# PMU.net
KiCad netlist of a schematic drawn in Altium Designer
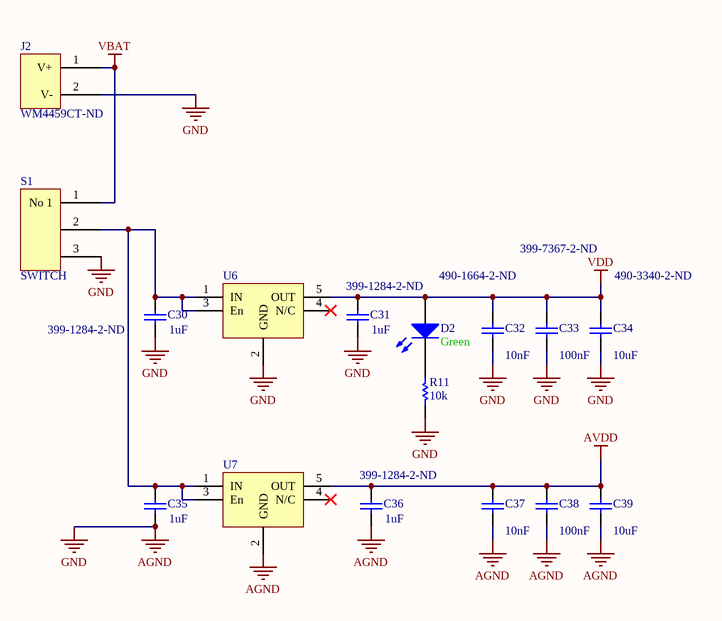
[diagram p0: PMU.SchDoc]

(export (version "E")
  (design (tool "Eeschema 10.0.6"))
  (components
    (comp (ref "C30")
      (value "1uF")
      (footprint "0402")
      (description "Capacitor (Semiconductor SIM Model)")
      (fields
        (field (name "SUPPLIER PART NUMBER 1") "399-1284-2-ND")
        (field (name "Comment") "Cap Semi")
        (field (name "PUBLISHER") "Altium Limited")
      )
      (libsource (lib "Miscellaneous Devices") (part "Cap Semi"))
    )
    (comp (ref "C31")
      (value "1uF")
      (footprint "0402")
      (description "Capacitor (Semiconductor SIM Model)")
      (fields
        (field (name "SUPPLIER PART NUMBER 1") "399-1284-2-ND")
        (field (name "Comment") "Cap Semi")
        (field (name "PUBLISHER") "Altium Limited")
      )
      (libsource (lib "Miscellaneous Devices") (part "Cap Semi"))
    )
    (comp (ref "C32")
      (value "10nF")
      (footprint "0402")
      (description "Capacitor (Semiconductor SIM Model)")
      (fields
        (field (name "SUPPLIER PART NUMBER 1") "490-1664-2-ND")
        (field (name "Comment") "Cap Semi")
        (field (name "PUBLISHER") "Altium Limited")
      )
      (libsource (lib "Miscellaneous Devices") (part "Cap Semi"))
    )
    (comp (ref "C33")
      (value "100nF")
      (footprint "0402")
      (description "Capacitor (Semiconductor SIM Model)")
      (fields
        (field (name "SUPPLIER PART NUMBER 1") "399-7367-2-ND")
        (field (name "Comment") "Cap Semi")
        (field (name "PUBLISHER") "Altium Limited")
      )
      (libsource (lib "Miscellaneous Devices") (part "Cap Semi"))
    )
    (comp (ref "C34")
      (value "10uF")
      (footprint "0402")
      (description "Capacitor (Semiconductor SIM Model)")
      (fields
        (field (name "SUPPLIER PART NUMBER 1") "490-3340-2-ND")
        (field (name "Comment") "Cap Semi")
        (field (name "PUBLISHER") "Altium Limited")
      )
      (libsource (lib "Miscellaneous Devices") (part "Cap Semi"))
    )
    (comp (ref "C35")
      (value "1uF")
      (footprint "0402")
      (description "Capacitor (Semiconductor SIM Model)")
      (fields (field (name "Comment") "Cap Semi") (field (name "PUBLISHER") "Altium Limited"))
      (libsource (lib "Miscellaneous Devices") (part "Cap Semi"))
    )
    (comp (ref "C36")
      (value "1uF")
      (footprint "0402")
      (description "Capacitor (Semiconductor SIM Model)")
      (fields
        (field (name "SUPPLIER PART NUMBER 1") "399-1284-2-ND")
        (field (name "Comment") "Cap Semi")
        (field (name "PUBLISHER") "Altium Limited")
      )
      (libsource (lib "Miscellaneous Devices") (part "Cap Semi"))
    )
    (comp (ref "C37")
      (value "10nF")
      (footprint "0402")
      (description "Capacitor (Semiconductor SIM Model)")
      (fields (field (name "Comment") "Cap Semi") (field (name "PUBLISHER") "Altium Limited"))
      (libsource (lib "Miscellaneous Devices") (part "Cap Semi"))
    )
    (comp (ref "C38")
      (value "100nF")
      (footprint "0402")
      (description "Capacitor (Semiconductor SIM Model)")
      (fields (field (name "Comment") "Cap Semi") (field (name "PUBLISHER") "Altium Limited"))
      (libsource (lib "Miscellaneous Devices") (part "Cap Semi"))
    )
    (comp (ref "C39")
      (value "10uF")
      (footprint "0402")
      (description "Capacitor (Semiconductor SIM Model)")
      (fields (field (name "Comment") "Cap Semi") (field (name "PUBLISHER") "Altium Limited"))
      (libsource (lib "Miscellaneous Devices") (part "Cap Semi"))
    )
    (comp (ref "D2")
      (value "~")
      (footprint "0402")
      (description "Typical BLUE SiC LED")
      (fields (field (name "COLOR") "Green") (field (name "PUBLISHER") "Altium Limited"))
      (libsource (lib "Miscellaneous Devices") (part "LED3"))
    )
    (comp (ref "J2")
      (value "WM4459CT-ND")
      (footprint "WM4459CT-ND")
      (libsource (lib "WM4459CT-ND") (part "WM4459CT-ND"))
    )
    (comp (ref "R11")
      (value "10k")
      (footprint "0402")
      (description "Semiconductor Resistor")
      (fields (field (name "PUBLISHER") "Altium Limited"))
      (libsource (lib "Miscellaneous Devices") (part "Res Semi"))
    )
    (comp (ref "S1") (value "SWITCH") (footprint "CUS-12B") (libsource (lib "CUS-12B") (part "Component_1")))
    (comp (ref "U6")
      (value "Reg 3.3V")
      (footprint "TSOP-5ll")
      (description "IC REG LDO 3.3V 0.3A 5TSOP")
      (libsource (lib "EMG_library") (part "NCP603SN330T1G"))
    )
    (comp (ref "U7")
      (value "Reg 3.3V")
      (footprint "TSOP-5ll")
      (description "IC REG LDO 3.3V 0.3A 5TSOP")
      (libsource (lib "EMG_library") (part "NCP603SN330T1G"))
    )
  )
  (nets
    (net (code "1") (name "AGND") (class "Default")
      (node (ref "C30") (pin "1") (pinfunction "1_1") (pintype "passive"))
      (node (ref "C31") (pin "1") (pinfunction "1_1") (pintype "passive"))
      (node (ref "C32") (pin "1") (pinfunction "1_1") (pintype "passive"))
      (node (ref "C33") (pin "1") (pinfunction "1_1") (pintype "passive"))
      (node (ref "C34") (pin "1") (pinfunction "1_1") (pintype "passive"))
      (node (ref "C35") (pin "1") (pinfunction "1_1") (pintype "passive"))
      (node (ref "C36") (pin "1") (pinfunction "1_1") (pintype "passive"))
      (node (ref "C37") (pin "1") (pinfunction "1_1") (pintype "passive"))
      (node (ref "C38") (pin "1") (pinfunction "1_1") (pintype "passive"))
      (node (ref "C39") (pin "1") (pinfunction "1_1") (pintype "passive"))
      (node (ref "J2") (pin "2") (pinfunction "V-_2") (pintype "passive"))
      (node (ref "R11") (pin "2") (pinfunction "2_2") (pintype "passive"))
      (node (ref "S1") (pin "3") (pinfunction "3_3") (pintype "passive"))
      (node (ref "U6") (pin "2") (pinfunction "GND_2") (pintype "power_in"))
      (node (ref "U7") (pin "2") (pinfunction "GND_2") (pintype "power_in"))
    )
    (net (code "2") (name "AVDD") (class "Default")
      (node (ref "C36") (pin "2") (pinfunction "2_2") (pintype "passive"))
      (node (ref "C37") (pin "2") (pinfunction "2_2") (pintype "passive"))
      (node (ref "C38") (pin "2") (pinfunction "2_2") (pintype "passive"))
      (node (ref "C39") (pin "2") (pinfunction "2_2") (pintype "passive"))
      (node (ref "U7") (pin "5") (pinfunction "OUT_5") (pintype "power_in"))
    )
    (net (code "3") (name "Net-(D2-K)") (class "Default")
      (node (ref "D2") (pin "2") (pinfunction "K_2") (pintype "passive"))
      (node (ref "R11") (pin "1") (pinfunction "1_1") (pintype "passive"))
    )
    (net (code "4") (name "Net-(U6-En)") (class "Default")
      (node (ref "C30") (pin "2") (pinfunction "2_2") (pintype "passive"))
      (node (ref "C35") (pin "2") (pinfunction "2_2") (pintype "passive"))
      (node (ref "S1") (pin "2") (pinfunction "2_2") (pintype "passive"))
      (node (ref "U6") (pin "1") (pinfunction "IN_1") (pintype "power_in"))
      (node (ref "U6") (pin "3") (pinfunction "En_3") (pintype "power_in"))
      (node (ref "U7") (pin "1") (pinfunction "IN_1") (pintype "power_in"))
      (node (ref "U7") (pin "3") (pinfunction "En_3") (pintype "power_in"))
    )
    (net (code "5") (name "VBAT") (class "Default")
      (node (ref "J2") (pin "1") (pinfunction "V+_1") (pintype "passive"))
      (node (ref "S1") (pin "1") (pinfunction "No_1_1") (pintype "passive"))
    )
    (net (code "6") (name "VDD") (class "Default")
      (node (ref "C31") (pin "2") (pinfunction "2_2") (pintype "passive"))
      (node (ref "C32") (pin "2") (pinfunction "2_2") (pintype "passive"))
      (node (ref "C33") (pin "2") (pinfunction "2_2") (pintype "passive"))
      (node (ref "C34") (pin "2") (pinfunction "2_2") (pintype "passive"))
      (node (ref "D2") (pin "1") (pinfunction "A_1") (pintype "passive"))
      (node (ref "U6") (pin "5") (pinfunction "OUT_5") (pintype "power_in"))
    )
    (net (code "7") (name "unconnected-(U6-N{slash}C-Pad4)") (class "Default")
      (node (ref "U6") (pin "4") (pinfunction "N/C_4") (pintype "power_in+no_connect"))
    )
    (net (code "8") (name "unconnected-(U7-N{slash}C-Pad4)") (class "Default")
      (node (ref "U7") (pin "4") (pinfunction "N/C_4") (pintype "power_in+no_connect"))
    )
  )
)
